# HA-NM5500A_20130.net
KiCad netlist of a schematic drawn in Altium Designer
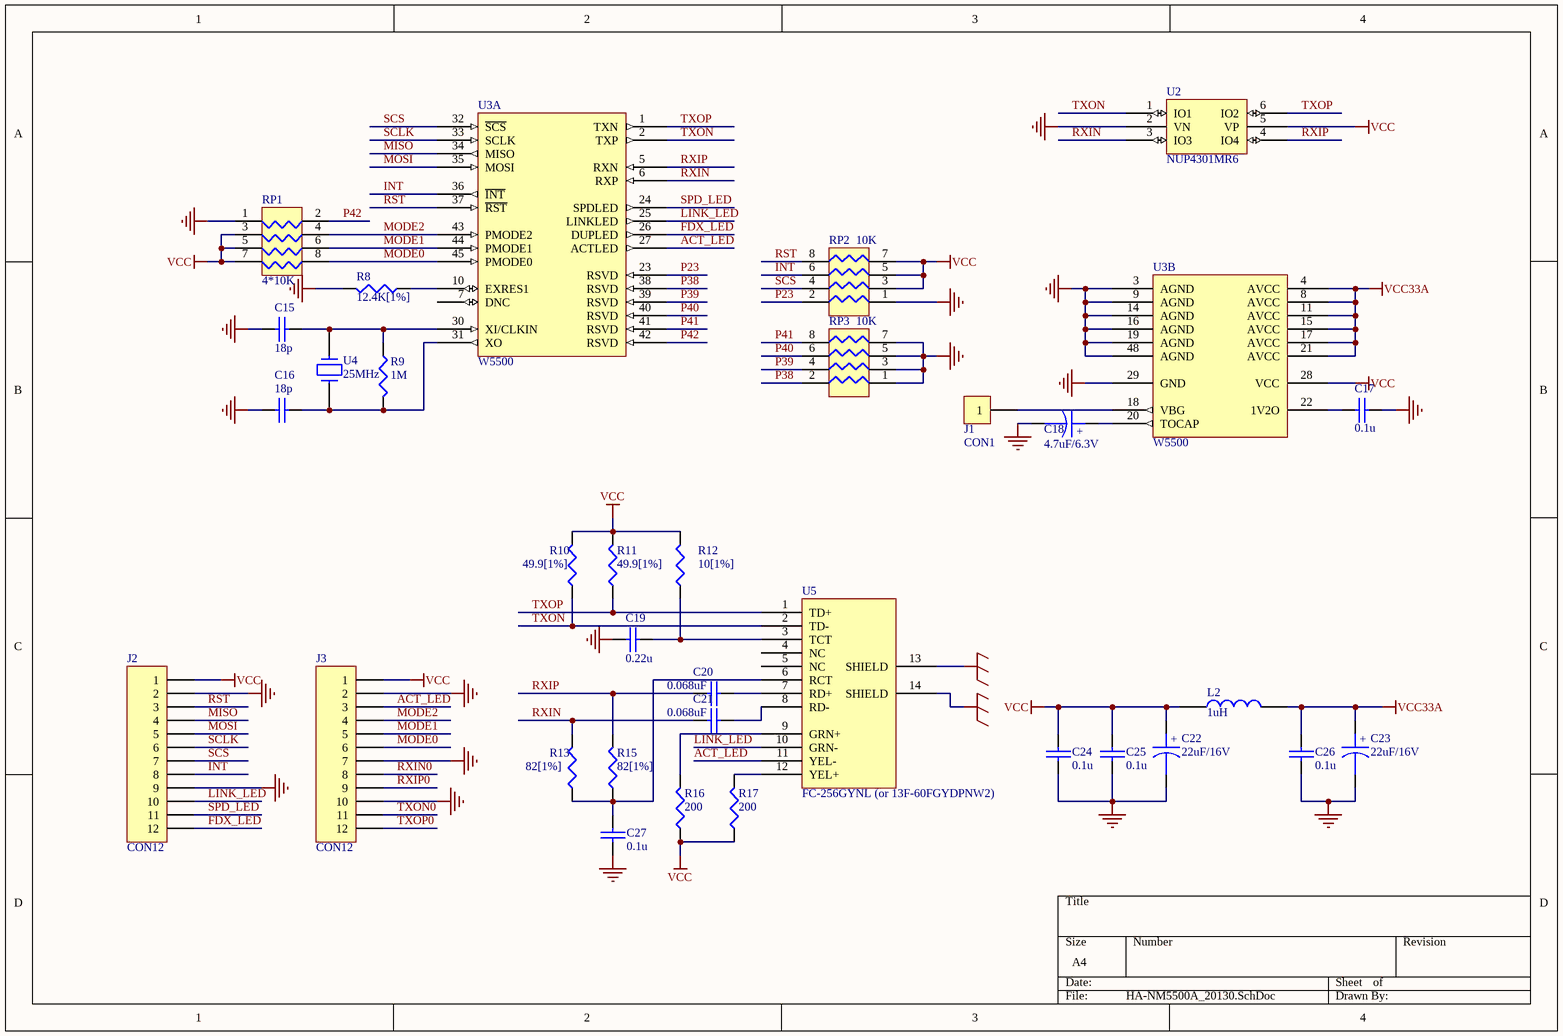
[diagram p0: HA-NM5500A_20130.SchDoc]

(export (version "E")
  (design (tool "Eeschema 10.0.6"))
  (components
    (comp (ref "C15")
      (value "18p")
      (footprint "0603")
      (description "Capacitor")
      (libsource (lib "*") (part "CAP"))
    )
    (comp (ref "C16")
      (value "18p")
      (footprint "0603")
      (description "Capacitor")
      (libsource (lib "*") (part "CAP"))
    )
    (comp (ref "C17")
      (value "0.1u")
      (footprint "0603")
      (description "Capacitor")
      (libsource (lib "*") (part "CAP"))
    )
    (comp (ref "C18")
      (value "4.7uF/6.3V")
      (footprint "CAP-B")
      (description "Capacitor")
      (libsource (lib "*") (part "CAPACITOR POL"))
    )
    (comp (ref "C19")
      (value "0.22u")
      (footprint "0603")
      (description "Capacitor")
      (libsource (lib "*") (part "CAP"))
    )
    (comp (ref "C20")
      (value "0.068uF")
      (footprint "0603")
      (description "Capacitor")
      (libsource (lib "*") (part "CAP"))
    )
    (comp (ref "C21")
      (value "0.068uF")
      (footprint "0603")
      (description "Capacitor")
      (libsource (lib "*") (part "CAP"))
    )
    (comp (ref "C22")
      (value "22uF/16V")
      (footprint "CAP-B")
      (description "Capacitor")
      (libsource (lib "*") (part "CAPACITOR POL"))
    )
    (comp (ref "C23")
      (value "22uF/16V")
      (footprint "CAP-B")
      (description "Capacitor")
      (libsource (lib "*") (part "CAPACITOR POL"))
    )
    (comp (ref "C24")
      (value "0.1u")
      (footprint "0603")
      (description "Capacitor")
      (libsource (lib "*") (part "CAP"))
    )
    (comp (ref "C25")
      (value "0.1u")
      (footprint "0603")
      (description "Capacitor")
      (libsource (lib "*") (part "CAP"))
    )
    (comp (ref "C26")
      (value "0.1u")
      (footprint "0603")
      (description "Capacitor")
      (libsource (lib "*") (part "CAP"))
    )
    (comp (ref "C27")
      (value "0.1u")
      (footprint "0603")
      (description "Capacitor")
      (libsource (lib "*") (part "CAP"))
    )
    (comp (ref "J1") (value "CON1") (description "Connector") (libsource (lib "*") (part "CON1")))
    (comp (ref "J2") (value "CON12") (description "Connector") (libsource (lib "*") (part "CON12")))
    (comp (ref "J3") (value "CON12") (description "Connector") (libsource (lib "*") (part "CON12")))
    (comp (ref "L2") (value "1uH") (footprint "0603") (libsource (lib "*") (part "INDUCTOR")))
    (comp (ref "R8") (value "12.4K[1%]") (footprint "0603") (libsource (lib "*") (part "RES1")))
    (comp (ref "R9") (value "1M") (footprint "0603") (libsource (lib "*") (part "RES1")))
    (comp (ref "R10") (value "49.9[1%]") (footprint "0603") (libsource (lib "*") (part "RES1")))
    (comp (ref "R11") (value "49.9[1%]") (footprint "0603") (libsource (lib "*") (part "RES1")))
    (comp (ref "R12") (value "10[1%]") (footprint "0603") (libsource (lib "*") (part "RES1")))
    (comp (ref "R13") (value "82[1%]") (footprint "0603") (libsource (lib "*") (part "RES1")))
    (comp (ref "R15") (value "82[1%]") (footprint "0603") (libsource (lib "*") (part "RES1")))
    (comp (ref "R16") (value "200") (footprint "0603") (libsource (lib "*") (part "RES1")))
    (comp (ref "R17") (value "200") (footprint "0603") (libsource (lib "*") (part "RES1")))
    (comp (ref "RP1")
      (value "4*10K")
      (footprint "4X0603")
      (description "RP8")
      (libsource (lib "*") (part "RP4"))
    )
    (comp (ref "RP2")
      (value "10K")
      (footprint "SIP9")
      (description "RP8")
      (libsource (lib "") (part "RP4_1"))
    )
    (comp (ref "RP3")
      (value "10K")
      (footprint "SIP9")
      (description "RP8")
      (libsource (lib "") (part "RP4_1"))
    )
    (comp (ref "U2")
      (value "NUP4301MR6")
      (footprint "TSOP-6")
      (description "NUP4301MR6T1")
      (libsource (lib "*") (part "NUP4301"))
    )
    (comp (ref "U3") (value "W5500") (footprint "LQFP-48") (libsource (lib "*") (part "W5500")))
    (comp (ref "U4")
      (value "25MHz")
      (footprint "XTAL")
      (description "Crystal")
      (libsource (lib "*") (part "CRYSTAL"))
    )
    (comp (ref "U5")
      (value "FC-256GYNL (or 13F-60FGYDPNW2)")
      (footprint "RJ45-2")
      (description "LU1T516")
      (libsource (lib "*") (part "LU1T516"))
    )
  )
  (nets
    (net (code "1") (name "/ACT_LED") (class "Default")
      (node (ref "J3") (pin "3") (pinfunction "3_3") (pintype "passive"))
      (node (ref "U3") (pin "27") (pinfunction "ACTLED_27") (pintype "output"))
      (node (ref "U5") (pin "11") (pinfunction "YEL-_11") (pintype "passive"))
    )
    (net (code "2") (name "/FDX_LED") (class "Default")
      (node (ref "J2") (pin "12") (pinfunction "12_12") (pintype "passive"))
      (node (ref "U3") (pin "26") (pinfunction "DUPLED_26") (pintype "output"))
    )
    (net (code "3") (name "/INT") (class "Default")
      (node (ref "J2") (pin "8") (pinfunction "8_8") (pintype "passive"))
      (node (ref "RP2") (pin "6") (pintype "passive"))
      (node (ref "U3") (pin "36") (pinfunction "~{INT}_36") (pintype "output"))
    )
    (net (code "4") (name "/LINK_LED") (class "Default")
      (node (ref "J2") (pin "10") (pinfunction "10_10") (pintype "passive"))
      (node (ref "U3") (pin "25") (pinfunction "LINKLED_25") (pintype "output"))
      (node (ref "U5") (pin "10") (pinfunction "GRN-_10") (pintype "passive"))
    )
    (net (code "5") (name "/MISO") (class "Default")
      (node (ref "J2") (pin "4") (pinfunction "4_4") (pintype "passive"))
      (node (ref "U3") (pin "34") (pinfunction "MISO_34") (pintype "output"))
    )
    (net (code "6") (name "/MODE0") (class "Default")
      (node (ref "J3") (pin "6") (pinfunction "6_6") (pintype "passive"))
      (node (ref "RP1") (pin "8") (pintype "passive"))
      (node (ref "U3") (pin "45") (pinfunction "PMODE0_45") (pintype "input"))
    )
    (net (code "7") (name "/MODE1") (class "Default")
      (node (ref "J3") (pin "5") (pinfunction "5_5") (pintype "passive"))
      (node (ref "RP1") (pin "6") (pintype "passive"))
      (node (ref "U3") (pin "44") (pinfunction "PMODE1_44") (pintype "input"))
    )
    (net (code "8") (name "/MODE2") (class "Default")
      (node (ref "J3") (pin "4") (pinfunction "4_4") (pintype "passive"))
      (node (ref "RP1") (pin "4") (pintype "passive"))
      (node (ref "U3") (pin "43") (pinfunction "PMODE2_43") (pintype "input"))
    )
    (net (code "9") (name "/MOSI") (class "Default")
      (node (ref "J2") (pin "5") (pinfunction "5_5") (pintype "passive"))
      (node (ref "U3") (pin "35") (pinfunction "MOSI_35") (pintype "input"))
    )
    (net (code "10") (name "/P23") (class "Default")
      (node (ref "RP2") (pin "2") (pintype "passive"))
      (node (ref "U3") (pin "23") (pinfunction "RSVD_23") (pintype "input"))
    )
    (net (code "11") (name "/P38") (class "Default")
      (node (ref "RP3") (pin "2") (pintype "passive"))
      (node (ref "U3") (pin "38") (pinfunction "RSVD_38") (pintype "input"))
    )
    (net (code "12") (name "/P39") (class "Default")
      (node (ref "RP3") (pin "4") (pintype "passive"))
      (node (ref "U3") (pin "39") (pinfunction "RSVD_39") (pintype "input"))
    )
    (net (code "13") (name "/P40") (class "Default")
      (node (ref "RP3") (pin "6") (pintype "passive"))
      (node (ref "U3") (pin "40") (pinfunction "RSVD_40") (pintype "input"))
    )
    (net (code "14") (name "/P41") (class "Default")
      (node (ref "RP3") (pin "8") (pintype "passive"))
      (node (ref "U3") (pin "41") (pinfunction "RSVD_41") (pintype "input"))
    )
    (net (code "15") (name "/P42") (class "Default")
      (node (ref "RP1") (pin "2") (pintype "passive"))
      (node (ref "U3") (pin "42") (pinfunction "RSVD_42") (pintype "input"))
    )
    (net (code "16") (name "/RST") (class "Default")
      (node (ref "J2") (pin "3") (pinfunction "3_3") (pintype "passive"))
      (node (ref "RP2") (pin "8") (pintype "passive"))
      (node (ref "U3") (pin "37") (pinfunction "~{RST}_37") (pintype "input"))
    )
    (net (code "17") (name "/RXIN") (class "Default")
      (node (ref "C21") (pin "1") (pinfunction "1_1") (pintype "passive"))
      (node (ref "R13") (pin "2") (pinfunction "2_2") (pintype "passive"))
      (node (ref "U2") (pin "3") (pinfunction "IO3_3") (pintype "bidirectional"))
      (node (ref "U3") (pin "6") (pinfunction "RXP_6") (pintype "input"))
    )
    (net (code "18") (name "/RXIN0") (class "Default")
      (node (ref "J3") (pin "8") (pinfunction "8_8") (pintype "passive"))
    )
    (net (code "19") (name "/RXIP") (class "Default")
      (node (ref "C20") (pin "1") (pinfunction "1_1") (pintype "passive"))
      (node (ref "R15") (pin "2") (pinfunction "2_2") (pintype "passive"))
      (node (ref "U2") (pin "4") (pinfunction "IO4_4") (pintype "bidirectional"))
      (node (ref "U3") (pin "5") (pinfunction "RXN_5") (pintype "input"))
    )
    (net (code "20") (name "/RXIP0") (class "Default")
      (node (ref "J3") (pin "9") (pinfunction "9_9") (pintype "passive"))
    )
    (net (code "21") (name "/SCLK") (class "Default")
      (node (ref "J2") (pin "6") (pinfunction "6_6") (pintype "passive"))
      (node (ref "U3") (pin "33") (pinfunction "SCLK_33") (pintype "input"))
    )
    (net (code "22") (name "/SCS") (class "Default")
      (node (ref "J2") (pin "7") (pinfunction "7_7") (pintype "passive"))
      (node (ref "RP2") (pin "4") (pintype "passive"))
      (node (ref "U3") (pin "32") (pinfunction "~{SCS}_32") (pintype "input"))
    )
    (net (code "23") (name "/SPD_LED") (class "Default")
      (node (ref "J2") (pin "11") (pinfunction "11_11") (pintype "passive"))
      (node (ref "U3") (pin "24") (pinfunction "SPDLED_24") (pintype "output"))
    )
    (net (code "24") (name "/TXON") (class "Default")
      (node (ref "R10") (pin "1") (pinfunction "1_1") (pintype "passive"))
      (node (ref "U2") (pin "1") (pinfunction "IO1_1") (pintype "bidirectional"))
      (node (ref "U3") (pin "2") (pinfunction "TXP_2") (pintype "output"))
      (node (ref "U5") (pin "2") (pinfunction "TD-_2") (pintype "passive"))
    )
    (net (code "25") (name "/TXON0") (class "Default")
      (node (ref "J3") (pin "11") (pinfunction "11_11") (pintype "passive"))
    )
    (net (code "26") (name "/TXOP") (class "Default")
      (node (ref "R11") (pin "1") (pinfunction "1_1") (pintype "passive"))
      (node (ref "U2") (pin "6") (pinfunction "IO2_6") (pintype "bidirectional"))
      (node (ref "U3") (pin "1") (pinfunction "TXN_1") (pintype "output"))
      (node (ref "U5") (pin "1") (pinfunction "TD+_1") (pintype "passive"))
    )
    (net (code "27") (name "/TXOP0") (class "Default")
      (node (ref "J3") (pin "12") (pinfunction "12_12") (pintype "passive"))
    )
    (net (code "28") (name "EGND") (class "Default")
      (node (ref "U5") (pin "13") (pinfunction "SHIELD_13") (pintype "passive"))
    )
    (net (code "29") (name "EGND1") (class "Default")
      (node (ref "U5") (pin "14") (pinfunction "SHIELD_14") (pintype "passive"))
    )
    (net (code "30") (name "GND") (class "Default")
      (node (ref "C15") (pin "2") (pinfunction "2_2") (pintype "passive"))
      (node (ref "C16") (pin "2") (pinfunction "2_2") (pintype "passive"))
      (node (ref "C17") (pin "1") (pinfunction "1_1") (pintype "passive"))
      (node (ref "C18") (pin "2") (pinfunction "2_2") (pintype "passive"))
      (node (ref "C19") (pin "1") (pinfunction "1_1") (pintype "passive"))
      (node (ref "C22") (pin "2") (pinfunction "2_2") (pintype "passive"))
      (node (ref "C23") (pin "2") (pinfunction "2_2") (pintype "passive"))
      (node (ref "C24") (pin "2") (pinfunction "2_2") (pintype "passive"))
      (node (ref "C25") (pin "2") (pinfunction "2_2") (pintype "passive"))
      (node (ref "C26") (pin "2") (pinfunction "2_2") (pintype "passive"))
      (node (ref "C27") (pin "2") (pinfunction "2_2") (pintype "passive"))
      (node (ref "J2") (pin "2") (pinfunction "2_2") (pintype "passive"))
      (node (ref "J2") (pin "9") (pinfunction "9_9") (pintype "passive"))
      (node (ref "J3") (pin "10") (pinfunction "10_10") (pintype "passive"))
      (node (ref "J3") (pin "2") (pinfunction "2_2") (pintype "passive"))
      (node (ref "J3") (pin "7") (pinfunction "7_7") (pintype "passive"))
      (node (ref "R8") (pin "2") (pinfunction "2_2") (pintype "passive"))
      (node (ref "RP1") (pin "1") (pintype "passive"))
      (node (ref "RP2") (pin "1") (pintype "passive"))
      (node (ref "RP3") (pin "1") (pintype "passive"))
      (node (ref "RP3") (pin "3") (pintype "passive"))
      (node (ref "RP3") (pin "5") (pintype "passive"))
      (node (ref "RP3") (pin "7") (pintype "passive"))
      (node (ref "U2") (pin "2") (pinfunction "VN_2") (pintype "passive"))
      (node (ref "U3") (pin "14") (pinfunction "AGND_14") (pintype "power_in"))
      (node (ref "U3") (pin "16") (pinfunction "AGND_16") (pintype "power_in"))
      (node (ref "U3") (pin "19") (pinfunction "AGND_19") (pintype "power_in"))
      (node (ref "U3") (pin "29") (pinfunction "GND_29") (pintype "power_in"))
      (node (ref "U3") (pin "3") (pinfunction "AGND_3") (pintype "power_in"))
      (node (ref "U3") (pin "48") (pinfunction "AGND_48") (pintype "power_in"))
      (node (ref "U3") (pin "9") (pinfunction "AGND_9") (pintype "power_in"))
    )
    (net (code "31") (name "Net-(U3A-EXRES1)") (class "Default")
      (node (ref "R8") (pin "1") (pinfunction "1_1") (pintype "passive"))
      (node (ref "U3") (pin "10") (pinfunction "EXRES1_10") (pintype "bidirectional"))
    )
    (net (code "32") (name "Net-(U3A-XI{slash}CLKIN)") (class "Default")
      (node (ref "C15") (pin "1") (pinfunction "1_1") (pintype "passive"))
      (node (ref "R9") (pin "1") (pinfunction "1_1") (pintype "passive"))
      (node (ref "U3") (pin "30") (pinfunction "XI/CLKIN_30") (pintype "input"))
      (node (ref "U4") (pin "1") (pinfunction "1_1") (pintype "passive"))
    )
    (net (code "33") (name "Net-(U3A-XO)") (class "Default")
      (node (ref "C16") (pin "1") (pinfunction "1_1") (pintype "passive"))
      (node (ref "R9") (pin "2") (pinfunction "2_2") (pintype "passive"))
      (node (ref "U3") (pin "31") (pinfunction "XO_31") (pintype "output"))
      (node (ref "U4") (pin "2") (pinfunction "2_2") (pintype "passive"))
    )
    (net (code "34") (name "Net-(U3B-1V2O)") (class "Default")
      (node (ref "C17") (pin "2") (pinfunction "2_2") (pintype "passive"))
      (node (ref "U3") (pin "22") (pinfunction "1V2O_22") (pintype "power_in"))
    )
    (net (code "35") (name "Net-(U3B-TOCAP)") (class "Default")
      (node (ref "C18") (pin "1") (pinfunction "1_1") (pintype "passive"))
      (node (ref "U3") (pin "20") (pinfunction "TOCAP_20") (pintype "output"))
    )
    (net (code "36") (name "Net-(U3B-VBG)") (class "Default")
      (node (ref "J1") (pin "1") (pinfunction "1_1") (pintype "passive"))
      (node (ref "U3") (pin "18") (pinfunction "VBG_18") (pintype "output"))
    )
    (net (code "37") (name "Net-(U5-GRN+)") (class "Default")
      (node (ref "R16") (pin "2") (pinfunction "2_2") (pintype "passive"))
      (node (ref "U5") (pin "9") (pinfunction "GRN+_9") (pintype "passive"))
    )
    (net (code "38") (name "Net-(U5-RCT)") (class "Default")
      (node (ref "C27") (pin "1") (pinfunction "1_1") (pintype "passive"))
      (node (ref "R13") (pin "1") (pinfunction "1_1") (pintype "passive"))
      (node (ref "R15") (pin "1") (pinfunction "1_1") (pintype "passive"))
      (node (ref "U5") (pin "6") (pinfunction "RCT_6") (pintype "passive"))
    )
    (net (code "39") (name "Net-(U5-RD+)") (class "Default")
      (node (ref "C20") (pin "2") (pinfunction "2_2") (pintype "passive"))
      (node (ref "U5") (pin "7") (pinfunction "RD+_7") (pintype "passive"))
    )
    (net (code "40") (name "Net-(U5-RD-)") (class "Default")
      (node (ref "C21") (pin "2") (pinfunction "2_2") (pintype "passive"))
      (node (ref "U5") (pin "8") (pinfunction "RD-_8") (pintype "passive"))
    )
    (net (code "41") (name "Net-(U5-TCT)") (class "Default")
      (node (ref "C19") (pin "2") (pinfunction "2_2") (pintype "passive"))
      (node (ref "R12") (pin "1") (pinfunction "1_1") (pintype "passive"))
      (node (ref "U5") (pin "3") (pinfunction "TCT_3") (pintype "passive"))
    )
    (net (code "42") (name "Net-(U5-YEL+)") (class "Default")
      (node (ref "R17") (pin "2") (pinfunction "2_2") (pintype "passive"))
      (node (ref "U5") (pin "12") (pinfunction "YEL+_12") (pintype "passive"))
    )
    (net (code "43") (name "VCC") (class "Default")
      (node (ref "C22") (pin "1") (pinfunction "1_1") (pintype "passive"))
      (node (ref "C24") (pin "1") (pinfunction "1_1") (pintype "passive"))
      (node (ref "C25") (pin "1") (pinfunction "1_1") (pintype "passive"))
      (node (ref "J2") (pin "1") (pinfunction "1_1") (pintype "passive"))
      (node (ref "J3") (pin "1") (pinfunction "1_1") (pintype "passive"))
      (node (ref "L2") (pin "1") (pinfunction "1_1") (pintype "passive"))
      (node (ref "R10") (pin "2") (pinfunction "2_2") (pintype "passive"))
      (node (ref "R11") (pin "2") (pinfunction "2_2") (pintype "passive"))
      (node (ref "R12") (pin "2") (pinfunction "2_2") (pintype "passive"))
      (node (ref "R16") (pin "1") (pinfunction "1_1") (pintype "passive"))
      (node (ref "R17") (pin "1") (pinfunction "1_1") (pintype "passive"))
      (node (ref "RP1") (pin "3") (pintype "passive"))
      (node (ref "RP1") (pin "5") (pintype "passive"))
      (node (ref "RP1") (pin "7") (pintype "passive"))
      (node (ref "RP2") (pin "3") (pintype "passive"))
      (node (ref "RP2") (pin "5") (pintype "passive"))
      (node (ref "RP2") (pin "7") (pintype "passive"))
      (node (ref "U2") (pin "5") (pinfunction "VP_5") (pintype "passive"))
      (node (ref "U3") (pin "28") (pinfunction "VCC_28") (pintype "power_in"))
    )
    (net (code "44") (name "VCC33A") (class "Default")
      (node (ref "C23") (pin "1") (pinfunction "1_1") (pintype "passive"))
      (node (ref "C26") (pin "1") (pinfunction "1_1") (pintype "passive"))
      (node (ref "L2") (pin "2") (pinfunction "2_2") (pintype "passive"))
      (node (ref "U3") (pin "11") (pinfunction "AVCC_11") (pintype "power_in"))
      (node (ref "U3") (pin "15") (pinfunction "AVCC_15") (pintype "power_in"))
      (node (ref "U3") (pin "17") (pinfunction "AVCC_17") (pintype "power_in"))
      (node (ref "U3") (pin "21") (pinfunction "AVCC_21") (pintype "power_in"))
      (node (ref "U3") (pin "4") (pinfunction "AVCC_4") (pintype "power_in"))
      (node (ref "U3") (pin "8") (pinfunction "AVCC_8") (pintype "power_in"))
    )
    (net (code "45") (name "unconnected-(U3A-DNC-Pad7)") (class "Default")
      (node (ref "U3") (pin "7") (pinfunction "DNC_7") (pintype "bidirectional"))
    )
    (net (code "46") (name "unconnected-(U5-NC-Pad4)") (class "Default")
      (node (ref "U5") (pin "4") (pinfunction "NC_4") (pintype "passive"))
    )
    (net (code "47") (name "unconnected-(U5-NC-Pad5)") (class "Default")
      (node (ref "U5") (pin "5") (pinfunction "NC_5") (pintype "passive"))
    )
  )
)
